# MPDS_board.net
KiCad netlist of a schematic drawn in EAGLE
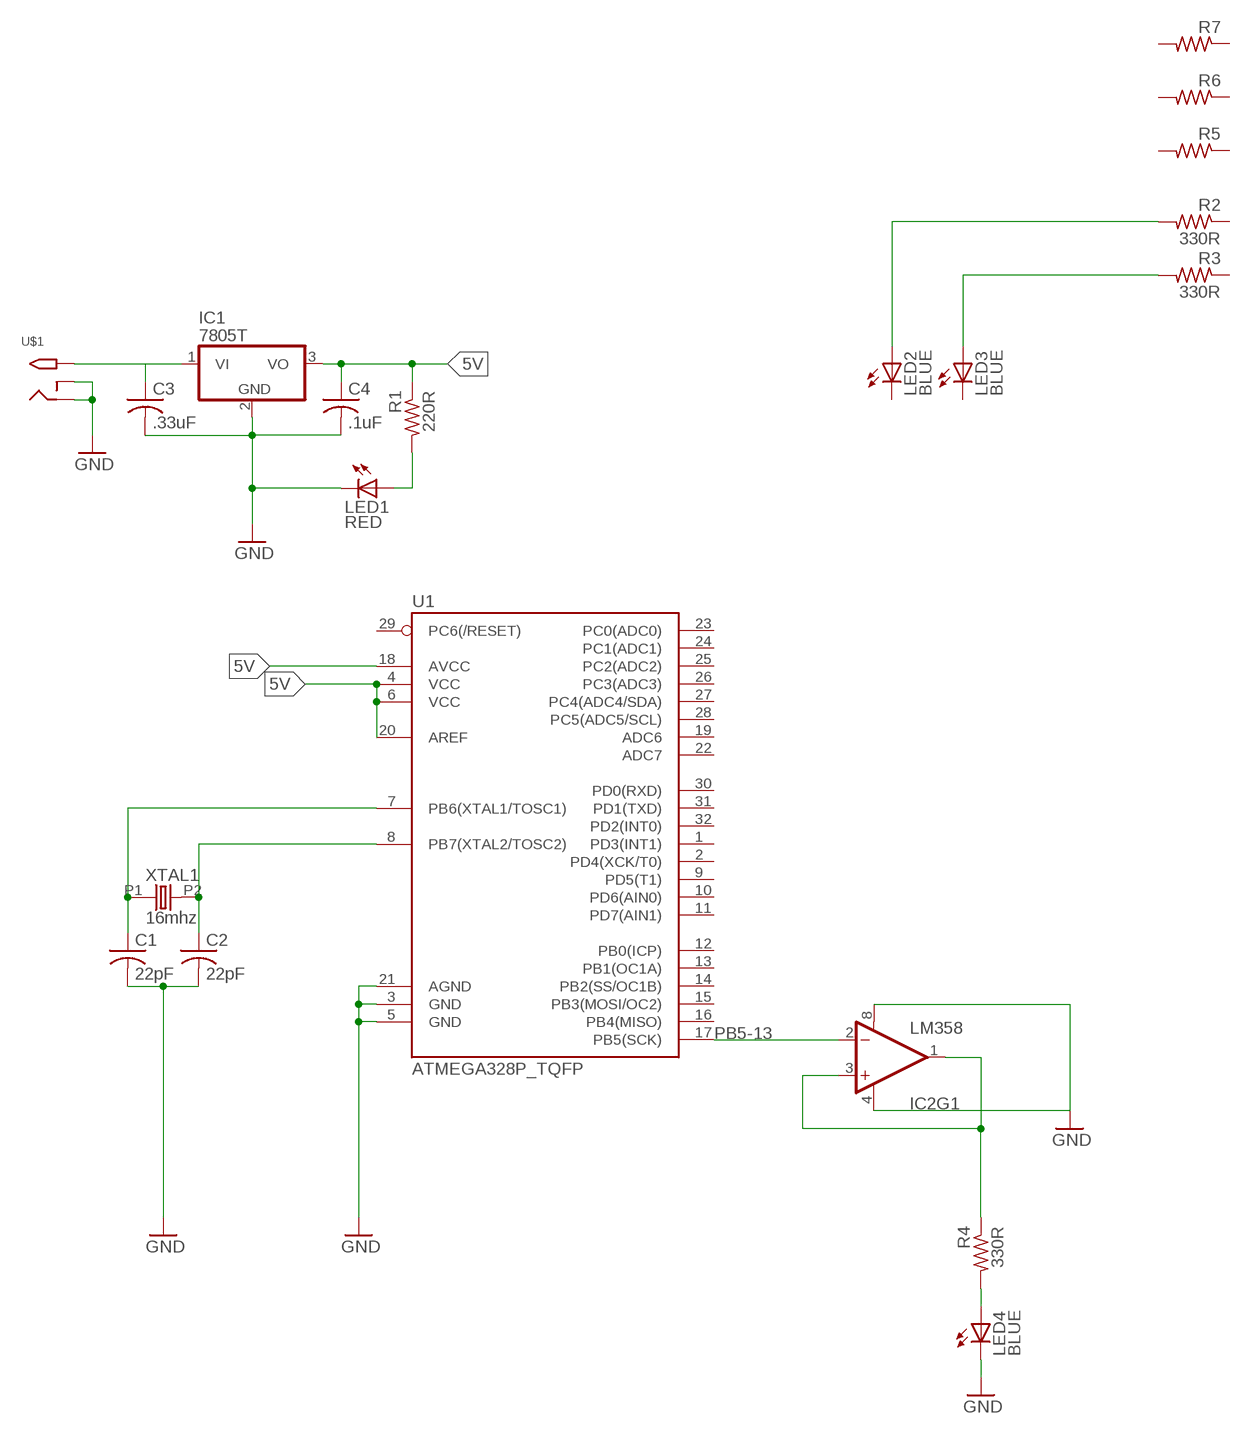
[diagram p0: schematic, sheet 1]

(export (version "E")
  (design (tool "Eeschema 10.0.6"))
  (components
    (comp (ref "C1")
      (value "22pF")
      (footprint "eagle-import:C050-025X075")
      (libsource (lib "eagle-import") (part "C-US050-025X075"))
    )
    (comp (ref "C2")
      (value "22pF")
      (footprint "eagle-import:C050-025X075")
      (libsource (lib "eagle-import") (part "C-US050-025X075"))
    )
    (comp (ref "C3")
      (value ".33uF")
      (footprint "eagle-import:C050-025X075")
      (libsource (lib "eagle-import") (part "C-US050-025X075"))
    )
    (comp (ref "C4")
      (value ".1uF")
      (footprint "eagle-import:C050-025X075")
      (libsource (lib "eagle-import") (part "C-US050-025X075"))
    )
    (comp (ref "IC1")
      (value "7805T")
      (footprint "eagle-import:TO220H")
      (libsource (lib "eagle-import") (part "78T05"))
    )
    (comp (ref "IC2")
      (value "LM358")
      (footprint "eagle-import:DIP08")
      (libsource (lib "eagle-import") (part "LM358"))
    )
    (comp (ref "LED1")
      (value "RED")
      (footprint "eagle-import:LED5MM")
      (libsource (lib "eagle-import") (part "LED5MM"))
    )
    (comp (ref "LED2")
      (value "BLUE")
      (footprint "eagle-import:LED5MM")
      (libsource (lib "eagle-import") (part "LED5MM"))
    )
    (comp (ref "LED3")
      (value "BLUE")
      (footprint "eagle-import:LED5MM")
      (libsource (lib "eagle-import") (part "LED5MM"))
    )
    (comp (ref "LED4")
      (value "BLUE")
      (footprint "eagle-import:LED5MM")
      (libsource (lib "eagle-import") (part "LED5MM"))
    )
    (comp (ref "R1")
      (value "220R")
      (footprint "eagle-import:0207_10")
      (libsource (lib "eagle-import") (part "R-US_0207/10"))
    )
    (comp (ref "R2")
      (value "330R")
      (footprint "eagle-import:0207_10")
      (libsource (lib "eagle-import") (part "R-US_0207/10"))
    )
    (comp (ref "R3")
      (value "330R")
      (footprint "eagle-import:0207_10")
      (libsource (lib "eagle-import") (part "R-US_0207/10"))
    )
    (comp (ref "R4")
      (value "330R")
      (footprint "eagle-import:0207_10")
      (libsource (lib "eagle-import") (part "R-US_0207/10"))
    )
    (comp (ref "R5")
      (value "R-US_0207/10")
      (footprint "eagle-import:0207_10")
      (libsource (lib "eagle-import") (part "R-US_0207/10"))
    )
    (comp (ref "R6")
      (value "R-US_0207/10")
      (footprint "eagle-import:0207_10")
      (libsource (lib "eagle-import") (part "R-US_0207/10"))
    )
    (comp (ref "R7")
      (value "R-US_0207/10")
      (footprint "eagle-import:0207_10")
      (libsource (lib "eagle-import") (part "R-US_0207/10"))
    )
    (comp (ref "U$1")
      (value "2.1MMJACKTHM")
      (footprint "eagle-import:PJ-102A")
      (libsource (lib "eagle-import") (part "2.1MMJACKTHM"))
    )
    (comp (ref "U1")
      (value "ATMEGA328P_TQFP")
      (footprint "eagle-import:TQFP32-08")
      (libsource (lib "eagle-import") (part "ATMEGA328P_TQFP"))
    )
    (comp (ref "XTAL1")
      (value "16mhz")
      (footprint "eagle-import:HC-49U-PTH")
      (libsource (lib "eagle-import") (part "OSC-XTAL-HC-49U-PTH"))
    )
  )
  (nets
    (net (code "1") (name "/PB5-13") (class "Default")
      (node (ref "IC2") (pin "2") (pinfunction "-IN_2") (pintype "input"))
      (node (ref "U1") (pin "17") (pinfunction "PB5(SCK)_17") (pintype "bidirectional"))
    )
    (net (code "2") (name "5V") (class "Default")
      (node (ref "C4") (pin "1") (pinfunction "1_1") (pintype "passive"))
      (node (ref "IC1") (pin "3") (pinfunction "VO_3") (pintype "passive"))
      (node (ref "R1") (pin "1") (pinfunction "1_1") (pintype "passive"))
      (node (ref "U1") (pin "18") (pinfunction "AVCC_18") (pintype "bidirectional"))
      (node (ref "U1") (pin "20") (pinfunction "AREF_20") (pintype "bidirectional"))
      (node (ref "U1") (pin "4") (pinfunction "VCC_4") (pintype "bidirectional"))
      (node (ref "U1") (pin "6") (pinfunction "VCC_6") (pintype "bidirectional"))
    )
    (net (code "3") (name "GND") (class "Default")
      (node (ref "C1") (pin "2") (pinfunction "2_2") (pintype "passive"))
      (node (ref "C2") (pin "2") (pinfunction "2_2") (pintype "passive"))
      (node (ref "C3") (pin "2") (pinfunction "2_2") (pintype "passive"))
      (node (ref "C4") (pin "2") (pinfunction "2_2") (pintype "passive"))
      (node (ref "IC1") (pin "2") (pinfunction "GND_2") (pintype "passive"))
      (node (ref "IC2") (pin "4") (pinfunction "V-_4") (pintype "power_in"))
      (node (ref "IC2") (pin "8") (pinfunction "V+_8") (pintype "power_in"))
      (node (ref "LED1") (pin "K") (pinfunction "C_K") (pintype "passive"))
      (node (ref "LED4") (pin "K") (pinfunction "C_K") (pintype "passive"))
      (node (ref "U$1") (pin "RING") (pinfunction "RING_RING") (pintype "bidirectional"))
      (node (ref "U$1") (pin "RING_SW") (pinfunction "RING_SW_RING_SW") (pintype "bidirectional"))
      (node (ref "U1") (pin "21") (pinfunction "AGND_21") (pintype "bidirectional"))
      (node (ref "U1") (pin "3") (pinfunction "GND_3") (pintype "bidirectional"))
      (node (ref "U1") (pin "5") (pinfunction "GND_5") (pintype "bidirectional"))
    )
    (net (code "4") (name "Net-(IC1-VI)") (class "Default")
      (node (ref "C3") (pin "1") (pinfunction "1_1") (pintype "passive"))
      (node (ref "IC1") (pin "1") (pinfunction "VI_1") (pintype "input"))
      (node (ref "U$1") (pin "TIP") (pinfunction "TIP_TIP") (pintype "bidirectional"))
    )
    (net (code "5") (name "Net-(IC2A-+IN)") (class "Default")
      (node (ref "IC2") (pin "1") (pinfunction "OUT_1") (pintype "output"))
      (node (ref "IC2") (pin "3") (pinfunction "+IN_3") (pintype "input"))
      (node (ref "R4") (pin "1") (pinfunction "1_1") (pintype "passive"))
    )
    (net (code "6") (name "Net-(LED1-PadA)") (class "Default")
      (node (ref "LED1") (pin "A") (pinfunction "A_A") (pintype "passive"))
      (node (ref "R1") (pin "2") (pinfunction "2_2") (pintype "passive"))
    )
    (net (code "7") (name "Net-(LED2-PadA)") (class "Default")
      (node (ref "LED2") (pin "A") (pinfunction "A_A") (pintype "passive"))
      (node (ref "R2") (pin "2") (pinfunction "2_2") (pintype "passive"))
    )
    (net (code "8") (name "Net-(LED3-PadA)") (class "Default")
      (node (ref "LED3") (pin "A") (pinfunction "A_A") (pintype "passive"))
      (node (ref "R3") (pin "2") (pinfunction "2_2") (pintype "passive"))
    )
    (net (code "9") (name "Net-(LED4-PadA)") (class "Default")
      (node (ref "LED4") (pin "A") (pinfunction "A_A") (pintype "passive"))
      (node (ref "R4") (pin "2") (pinfunction "2_2") (pintype "passive"))
    )
    (net (code "10") (name "Net-(U1-PB6(XTAL1{slash}TOSC1))") (class "Default")
      (node (ref "C1") (pin "1") (pinfunction "1_1") (pintype "passive"))
      (node (ref "U1") (pin "7") (pinfunction "PB6(XTAL1/TOSC1)_7") (pintype "bidirectional"))
      (node (ref "XTAL1") (pin "P1") (pinfunction "1_P1") (pintype "passive"))
    )
    (net (code "11") (name "Net-(U1-PB7(XTAL2{slash}TOSC2))") (class "Default")
      (node (ref "C2") (pin "1") (pinfunction "1_1") (pintype "passive"))
      (node (ref "U1") (pin "8") (pinfunction "PB7(XTAL2/TOSC2)_8") (pintype "bidirectional"))
      (node (ref "XTAL1") (pin "P2") (pinfunction "2_P2") (pintype "passive"))
    )
    (net (code "12") (name "unconnected-(LED2-C-PadK)") (class "Default")
      (node (ref "LED2") (pin "K") (pinfunction "C_K") (pintype "passive"))
    )
    (net (code "13") (name "unconnected-(LED3-C-PadK)") (class "Default")
      (node (ref "LED3") (pin "K") (pinfunction "C_K") (pintype "passive"))
    )
    (net (code "14") (name "unconnected-(R2-Pad1)") (class "Default")
      (node (ref "R2") (pin "1") (pinfunction "1_1") (pintype "passive"))
    )
    (net (code "15") (name "unconnected-(R3-Pad1)") (class "Default")
      (node (ref "R3") (pin "1") (pinfunction "1_1") (pintype "passive"))
    )
    (net (code "16") (name "unconnected-(R5-Pad1)") (class "Default")
      (node (ref "R5") (pin "1") (pinfunction "1_1") (pintype "passive"))
    )
    (net (code "17") (name "unconnected-(R5-Pad2)") (class "Default")
      (node (ref "R5") (pin "2") (pinfunction "2_2") (pintype "passive"))
    )
    (net (code "18") (name "unconnected-(R6-Pad1)") (class "Default")
      (node (ref "R6") (pin "1") (pinfunction "1_1") (pintype "passive"))
    )
    (net (code "19") (name "unconnected-(R6-Pad2)") (class "Default")
      (node (ref "R6") (pin "2") (pinfunction "2_2") (pintype "passive"))
    )
    (net (code "20") (name "unconnected-(R7-Pad1)") (class "Default")
      (node (ref "R7") (pin "1") (pinfunction "1_1") (pintype "passive"))
    )
    (net (code "21") (name "unconnected-(R7-Pad2)") (class "Default")
      (node (ref "R7") (pin "2") (pinfunction "2_2") (pintype "passive"))
    )
    (net (code "22") (name "unconnected-(U1-ADC6-Pad19)") (class "Default")
      (node (ref "U1") (pin "19") (pinfunction "ADC6_19") (pintype "bidirectional"))
    )
    (net (code "23") (name "unconnected-(U1-ADC7-Pad22)") (class "Default")
      (node (ref "U1") (pin "22") (pinfunction "ADC7_22") (pintype "bidirectional"))
    )
    (net (code "24") (name "unconnected-(U1-PB0(ICP)-Pad12)") (class "Default")
      (node (ref "U1") (pin "12") (pinfunction "PB0(ICP)_12") (pintype "bidirectional"))
    )
    (net (code "25") (name "unconnected-(U1-PB1(OC1A)-Pad13)") (class "Default")
      (node (ref "U1") (pin "13") (pinfunction "PB1(OC1A)_13") (pintype "bidirectional"))
    )
    (net (code "26") (name "unconnected-(U1-PB2(SS{slash}OC1B)-Pad14)") (class "Default")
      (node (ref "U1") (pin "14") (pinfunction "PB2(SS/OC1B)_14") (pintype "bidirectional"))
    )
    (net (code "27") (name "unconnected-(U1-PB3(MOSI{slash}OC2)-Pad15)") (class "Default")
      (node (ref "U1") (pin "15") (pinfunction "PB3(MOSI/OC2)_15") (pintype "bidirectional"))
    )
    (net (code "28") (name "unconnected-(U1-PB4(MISO)-Pad16)") (class "Default")
      (node (ref "U1") (pin "16") (pinfunction "PB4(MISO)_16") (pintype "bidirectional"))
    )
    (net (code "29") (name "unconnected-(U1-PC0(ADC0)-Pad23)") (class "Default")
      (node (ref "U1") (pin "23") (pinfunction "PC0(ADC0)_23") (pintype "bidirectional"))
    )
    (net (code "30") (name "unconnected-(U1-PC1(ADC1)-Pad24)") (class "Default")
      (node (ref "U1") (pin "24") (pinfunction "PC1(ADC1)_24") (pintype "bidirectional"))
    )
    (net (code "31") (name "unconnected-(U1-PC2(ADC2)-Pad25)") (class "Default")
      (node (ref "U1") (pin "25") (pinfunction "PC2(ADC2)_25") (pintype "bidirectional"))
    )
    (net (code "32") (name "unconnected-(U1-PC3(ADC3)-Pad26)") (class "Default")
      (node (ref "U1") (pin "26") (pinfunction "PC3(ADC3)_26") (pintype "bidirectional"))
    )
    (net (code "33") (name "unconnected-(U1-PC4(ADC4{slash}SDA)-Pad27)") (class "Default")
      (node (ref "U1") (pin "27") (pinfunction "PC4(ADC4/SDA)_27") (pintype "bidirectional"))
    )
    (net (code "34") (name "unconnected-(U1-PC5(ADC5{slash}SCL)-Pad28)") (class "Default")
      (node (ref "U1") (pin "28") (pinfunction "PC5(ADC5/SCL)_28") (pintype "bidirectional"))
    )
    (net (code "35") (name "unconnected-(U1-PC6({slash}RESET)-Pad29)") (class "Default")
      (node (ref "U1") (pin "29") (pinfunction "PC6(/RESET)_29") (pintype "bidirectional"))
    )
    (net (code "36") (name "unconnected-(U1-PD0(RXD)-Pad30)") (class "Default")
      (node (ref "U1") (pin "30") (pinfunction "PD0(RXD)_30") (pintype "bidirectional"))
    )
    (net (code "37") (name "unconnected-(U1-PD1(TXD)-Pad31)") (class "Default")
      (node (ref "U1") (pin "31") (pinfunction "PD1(TXD)_31") (pintype "bidirectional"))
    )
    (net (code "38") (name "unconnected-(U1-PD2(INT0)-Pad32)") (class "Default")
      (node (ref "U1") (pin "32") (pinfunction "PD2(INT0)_32") (pintype "bidirectional"))
    )
    (net (code "39") (name "unconnected-(U1-PD3(INT1)-Pad1)") (class "Default")
      (node (ref "U1") (pin "1") (pinfunction "PD3(INT1)_1") (pintype "bidirectional"))
    )
    (net (code "40") (name "unconnected-(U1-PD4(XCK{slash}T0)-Pad2)") (class "Default")
      (node (ref "U1") (pin "2") (pinfunction "PD4(XCK/T0)_2") (pintype "bidirectional"))
    )
    (net (code "41") (name "unconnected-(U1-PD5(T1)-Pad9)") (class "Default")
      (node (ref "U1") (pin "9") (pinfunction "PD5(T1)_9") (pintype "bidirectional"))
    )
    (net (code "42") (name "unconnected-(U1-PD6(AIN0)-Pad10)") (class "Default")
      (node (ref "U1") (pin "10") (pinfunction "PD6(AIN0)_10") (pintype "bidirectional"))
    )
    (net (code "43") (name "unconnected-(U1-PD7(AIN1)-Pad11)") (class "Default")
      (node (ref "U1") (pin "11") (pinfunction "PD7(AIN1)_11") (pintype "bidirectional"))
    )
  )
)
